# Capacitacion_SMD.net
KiCad netlist of a schematic drawn in EAGLE
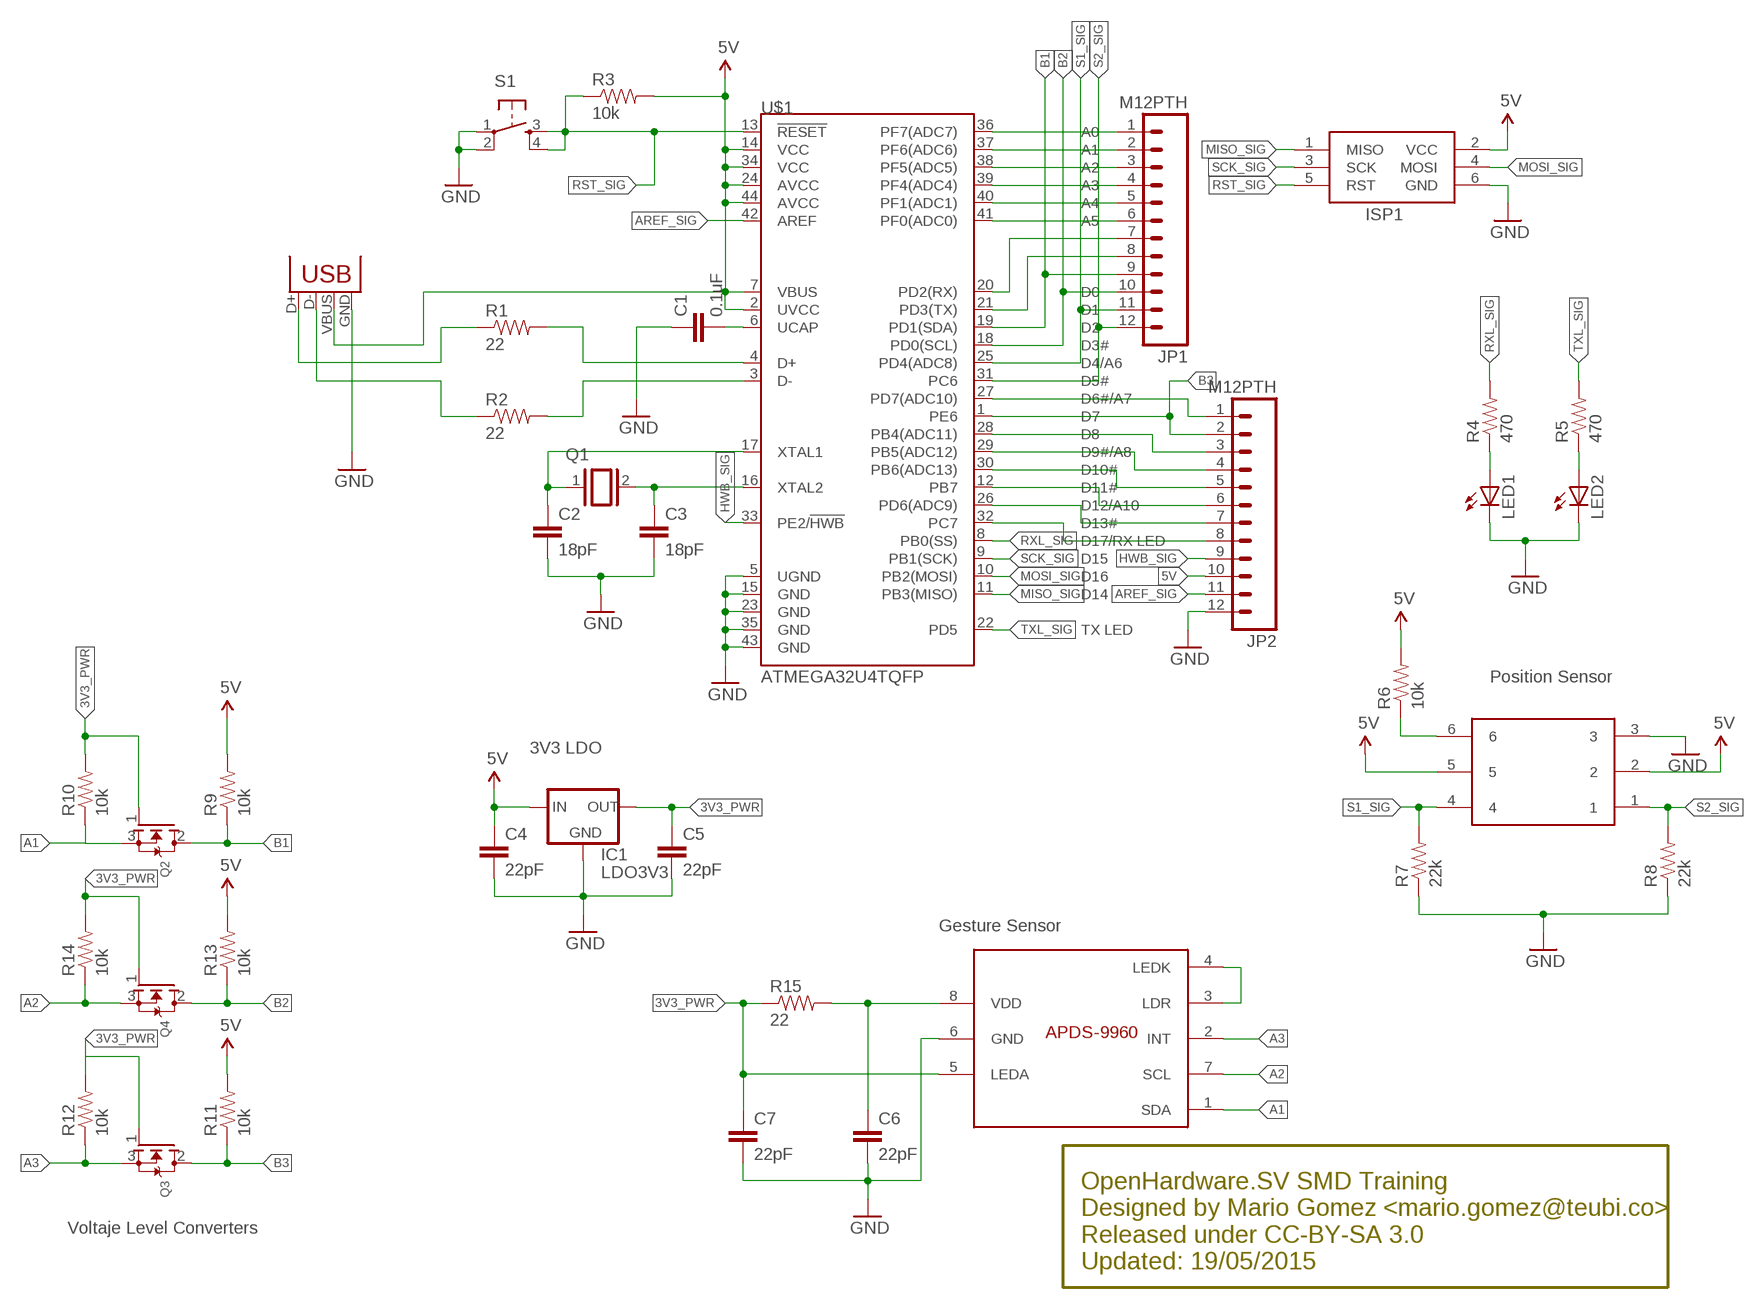
[diagram p0: schematic, sheet 1]

(export (version "E")
  (design (tool "Eeschema 10.0.6"))
  (components
    (comp (ref "C1")
      (value "0.1uF")
      (footprint "eagle-import:CAP-PTH-SMALL-KIT")
      (libsource (lib "eagle-import") (part "0.1UF-50V-20%(PTH)KIT-EZ"))
    )
    (comp (ref "C2")
      (value "18pF")
      (footprint "eagle-import:CAP-PTH-SMALL-KIT")
      (libsource (lib "eagle-import") (part "0.1UF-50V-20%(PTH)KIT-EZ"))
    )
    (comp (ref "C3")
      (value "18pF")
      (footprint "eagle-import:CAP-PTH-SMALL-KIT")
      (libsource (lib "eagle-import") (part "0.1UF-50V-20%(PTH)KIT-EZ"))
    )
    (comp (ref "C4")
      (value "22pF")
      (footprint "eagle-import:CAP-PTH-SMALL-KIT")
      (libsource (lib "eagle-import") (part "0.1UF-50V-20%(PTH)KIT-EZ"))
    )
    (comp (ref "C5")
      (value "22pF")
      (footprint "eagle-import:CAP-PTH-SMALL-KIT")
      (libsource (lib "eagle-import") (part "0.1UF-50V-20%(PTH)KIT-EZ"))
    )
    (comp (ref "C6")
      (value "22pF")
      (footprint "eagle-import:CAP-PTH-SMALL-KIT")
      (libsource (lib "eagle-import") (part "0.1UF-50V-20%(PTH)KIT-EZ"))
    )
    (comp (ref "C7")
      (value "22pF")
      (footprint "eagle-import:CAP-PTH-SMALL-KIT")
      (libsource (lib "eagle-import") (part "0.1UF-50V-20%(PTH)KIT-EZ"))
    )
    (comp (ref "IC1")
      (value "LDO3V3")
      (footprint "eagle-import:78XXL")
      (libsource (lib "eagle-import") (part "78XXL"))
    )
    (comp (ref "ISP1")
      (value "AVRISP-6")
      (footprint "eagle-import:AVRISP")
      (libsource (lib "eagle-import") (part "AVRISP-6"))
    )
    (comp (ref "JP1")
      (value "M12PTH")
      (footprint "eagle-import:1X12")
      (libsource (lib "eagle-import") (part "M12PTH"))
    )
    (comp (ref "JP2")
      (value "M12PTH")
      (footprint "eagle-import:1X12")
      (libsource (lib "eagle-import") (part "M12PTH"))
    )
    (comp (ref "LED1")
      (value "LED5MM")
      (footprint "eagle-import:LED5MM")
      (libsource (lib "eagle-import") (part "LED5MM"))
    )
    (comp (ref "LED2")
      (value "LED5MM")
      (footprint "eagle-import:LED5MM")
      (libsource (lib "eagle-import") (part "LED5MM"))
    )
    (comp (ref "Q1")
      (value "XTAL/S")
      (footprint "eagle-import:QS")
      (libsource (lib "eagle-import") (part "XTAL/S"))
    )
    (comp (ref "Q2")
      (value "MOSFET-NGDS_TO220V")
      (footprint "eagle-import:TO220V")
      (libsource (lib "eagle-import") (part "MOSFET-NGDS_TO220V"))
    )
    (comp (ref "Q3")
      (value "MOSFET-NGDS_TO220V")
      (footprint "eagle-import:TO220V")
      (libsource (lib "eagle-import") (part "MOSFET-NGDS_TO220V"))
    )
    (comp (ref "Q4")
      (value "MOSFET-NGDS_TO220V")
      (footprint "eagle-import:TO220V")
      (libsource (lib "eagle-import") (part "MOSFET-NGDS_TO220V"))
    )
    (comp (ref "R1")
      (value "22")
      (footprint "eagle-import:AXIAL-0.3")
      (libsource (lib "eagle-import") (part "RESISTORAXIAL-0.3"))
    )
    (comp (ref "R2")
      (value "22")
      (footprint "eagle-import:AXIAL-0.3")
      (libsource (lib "eagle-import") (part "RESISTORAXIAL-0.3"))
    )
    (comp (ref "R3")
      (value "10k")
      (footprint "eagle-import:AXIAL-0.3")
      (libsource (lib "eagle-import") (part "RESISTORAXIAL-0.3"))
    )
    (comp (ref "R4")
      (value "470")
      (footprint "eagle-import:AXIAL-0.3")
      (libsource (lib "eagle-import") (part "RESISTORAXIAL-0.3"))
    )
    (comp (ref "R5")
      (value "470")
      (footprint "eagle-import:AXIAL-0.3")
      (libsource (lib "eagle-import") (part "RESISTORAXIAL-0.3"))
    )
    (comp (ref "R6")
      (value "10k")
      (footprint "eagle-import:AXIAL-0.3")
      (libsource (lib "eagle-import") (part "RESISTORAXIAL-0.3"))
    )
    (comp (ref "R7")
      (value "22k")
      (footprint "eagle-import:AXIAL-0.3")
      (libsource (lib "eagle-import") (part "RESISTORAXIAL-0.3"))
    )
    (comp (ref "R8")
      (value "22k")
      (footprint "eagle-import:AXIAL-0.3")
      (libsource (lib "eagle-import") (part "RESISTORAXIAL-0.3"))
    )
    (comp (ref "R9")
      (value "10k")
      (footprint "eagle-import:AXIAL-0.3")
      (libsource (lib "eagle-import") (part "RESISTORAXIAL-0.3"))
    )
    (comp (ref "R10")
      (value "10k")
      (footprint "eagle-import:AXIAL-0.3")
      (libsource (lib "eagle-import") (part "RESISTORAXIAL-0.3"))
    )
    (comp (ref "R11")
      (value "10k")
      (footprint "eagle-import:AXIAL-0.3")
      (libsource (lib "eagle-import") (part "RESISTORAXIAL-0.3"))
    )
    (comp (ref "R12")
      (value "10k")
      (footprint "eagle-import:AXIAL-0.3")
      (libsource (lib "eagle-import") (part "RESISTORAXIAL-0.3"))
    )
    (comp (ref "R13")
      (value "10k")
      (footprint "eagle-import:AXIAL-0.3")
      (libsource (lib "eagle-import") (part "RESISTORAXIAL-0.3"))
    )
    (comp (ref "R14")
      (value "10k")
      (footprint "eagle-import:AXIAL-0.3")
      (libsource (lib "eagle-import") (part "RESISTORAXIAL-0.3"))
    )
    (comp (ref "R15")
      (value "22")
      (footprint "eagle-import:AXIAL-0.3")
      (libsource (lib "eagle-import") (part "RESISTORAXIAL-0.3"))
    )
    (comp (ref "S1")
      (value "TAC_SWITCHPTH")
      (footprint "eagle-import:TACTILE-PTH")
      (libsource (lib "eagle-import") (part "TAC_SWITCHPTH"))
    )
    (comp (ref "U$1")
      (value "ATMEGA32U4TQFP")
      (footprint "eagle-import:SPARKFUN-DIGITALIC_TQFP44")
      (libsource (lib "eagle-import") (part "ATMEGA32U4TQFP"))
    )
    (comp (ref "U$2")
      (value "USBPTH")
      (footprint "eagle-import:USB-B-PTH")
      (libsource (lib "eagle-import") (part "USBPTH"))
    )
    (comp (ref "U$3")
      (value "RPI-1031")
      (footprint "eagle-import:RPI-1031")
      (libsource (lib "eagle-import") (part "RPI-1031"))
    )
    (comp (ref "U$4")
      (value "APDS-9960")
      (footprint "eagle-import:APDS-9960")
      (libsource (lib "eagle-import") (part "APDS-9960"))
    )
  )
  (nets
    (net (code "1") (name "3V3_PWR") (class "Default")
      (node (ref "C5") (pin "1") (pinfunction "1_1") (pintype "passive"))
      (node (ref "C7") (pin "1") (pinfunction "1_1") (pintype "passive"))
      (node (ref "IC1") (pin "OUT") (pinfunction "OUT_OUT") (pintype "passive"))
      (node (ref "Q2") (pin "1") (pinfunction "G_1") (pintype "bidirectional"))
      (node (ref "Q3") (pin "1") (pinfunction "G_1") (pintype "bidirectional"))
      (node (ref "Q4") (pin "1") (pinfunction "G_1") (pintype "bidirectional"))
      (node (ref "R10") (pin "P$2") (pinfunction "2_P$2") (pintype "passive"))
      (node (ref "R12") (pin "P$2") (pinfunction "2_P$2") (pintype "passive"))
      (node (ref "R14") (pin "P$2") (pinfunction "2_P$2") (pintype "passive"))
      (node (ref "R15") (pin "P$1") (pinfunction "1_P$1") (pintype "passive"))
      (node (ref "U$4") (pin "5") (pinfunction "LEDA_5") (pintype "bidirectional"))
    )
    (net (code "2") (name "5V") (class "Default")
      (node (ref "C4") (pin "1") (pinfunction "1_1") (pintype "passive"))
      (node (ref "IC1") (pin "IN") (pinfunction "IN_IN") (pintype "input"))
      (node (ref "ISP1") (pin "2") (pinfunction "VCC_2") (pintype "power_in"))
      (node (ref "JP2") (pin "10") (pinfunction "10_10") (pintype "passive"))
      (node (ref "R11") (pin "P$2") (pinfunction "2_P$2") (pintype "passive"))
      (node (ref "R13") (pin "P$2") (pinfunction "2_P$2") (pintype "passive"))
      (node (ref "R3") (pin "P$2") (pinfunction "2_P$2") (pintype "passive"))
      (node (ref "R6") (pin "P$2") (pinfunction "2_P$2") (pintype "passive"))
      (node (ref "R9") (pin "P$2") (pinfunction "2_P$2") (pintype "passive"))
      (node (ref "U$1") (pin "14") (pinfunction "VCC_14") (pintype "bidirectional"))
      (node (ref "U$1") (pin "2") (pinfunction "UVCC_2") (pintype "bidirectional"))
      (node (ref "U$1") (pin "24") (pinfunction "AVCC_24") (pintype "bidirectional"))
      (node (ref "U$1") (pin "34") (pinfunction "VCC_34") (pintype "bidirectional"))
      (node (ref "U$1") (pin "44") (pinfunction "AVCC_44") (pintype "bidirectional"))
      (node (ref "U$1") (pin "7") (pinfunction "VBUS_7") (pintype "bidirectional"))
      (node (ref "U$2") (pin "VBUS") (pinfunction "VBUS_VBUS") (pintype "bidirectional"))
      (node (ref "U$3") (pin "2") (pinfunction "2_2") (pintype "bidirectional"))
      (node (ref "U$3") (pin "5") (pinfunction "5_5") (pintype "bidirectional"))
    )
    (net (code "3") (name "A1") (class "Default")
      (node (ref "Q2") (pin "3") (pinfunction "S_3") (pintype "bidirectional"))
      (node (ref "R10") (pin "P$1") (pinfunction "1_P$1") (pintype "passive"))
      (node (ref "U$4") (pin "1") (pinfunction "SDA_1") (pintype "bidirectional"))
    )
    (net (code "4") (name "A2") (class "Default")
      (node (ref "Q4") (pin "3") (pinfunction "S_3") (pintype "bidirectional"))
      (node (ref "R14") (pin "P$1") (pinfunction "1_P$1") (pintype "passive"))
      (node (ref "U$4") (pin "7") (pinfunction "SCL_7") (pintype "bidirectional"))
    )
    (net (code "5") (name "A3") (class "Default")
      (node (ref "Q3") (pin "3") (pinfunction "S_3") (pintype "bidirectional"))
      (node (ref "R12") (pin "P$1") (pinfunction "1_P$1") (pintype "passive"))
      (node (ref "U$4") (pin "2") (pinfunction "INT_2") (pintype "bidirectional"))
    )
    (net (code "6") (name "AREF_SIG") (class "Default")
      (node (ref "JP2") (pin "11") (pinfunction "11_11") (pintype "passive"))
      (node (ref "U$1") (pin "42") (pinfunction "AREF_42") (pintype "bidirectional"))
    )
    (net (code "7") (name "B1") (class "Default")
      (node (ref "JP1") (pin "9") (pinfunction "9_9") (pintype "passive"))
      (node (ref "Q2") (pin "2") (pinfunction "D_2") (pintype "bidirectional"))
      (node (ref "R9") (pin "P$1") (pinfunction "1_P$1") (pintype "passive"))
      (node (ref "U$1") (pin "19") (pinfunction "PD1(SDA)_19") (pintype "bidirectional"))
    )
    (net (code "8") (name "B2") (class "Default")
      (node (ref "JP1") (pin "10") (pinfunction "10_10") (pintype "passive"))
      (node (ref "Q4") (pin "2") (pinfunction "D_2") (pintype "bidirectional"))
      (node (ref "R13") (pin "P$1") (pinfunction "1_P$1") (pintype "passive"))
      (node (ref "U$1") (pin "18") (pinfunction "PD0(SCL)_18") (pintype "bidirectional"))
    )
    (net (code "9") (name "B3") (class "Default")
      (node (ref "JP2") (pin "2") (pinfunction "2_2") (pintype "passive"))
      (node (ref "Q3") (pin "2") (pinfunction "D_2") (pintype "bidirectional"))
      (node (ref "R11") (pin "P$1") (pinfunction "1_P$1") (pintype "passive"))
      (node (ref "U$1") (pin "1") (pinfunction "PE6_1") (pintype "bidirectional"))
    )
    (net (code "10") (name "GND") (class "Default")
      (node (ref "C1") (pin "1") (pinfunction "1_1") (pintype "passive"))
      (node (ref "C2") (pin "2") (pinfunction "2_2") (pintype "passive"))
      (node (ref "C3") (pin "2") (pinfunction "2_2") (pintype "passive"))
      (node (ref "C4") (pin "2") (pinfunction "2_2") (pintype "passive"))
      (node (ref "C5") (pin "2") (pinfunction "2_2") (pintype "passive"))
      (node (ref "C6") (pin "2") (pinfunction "2_2") (pintype "passive"))
      (node (ref "C7") (pin "2") (pinfunction "2_2") (pintype "passive"))
      (node (ref "IC1") (pin "GND") (pinfunction "GND_GND") (pintype "input"))
      (node (ref "ISP1") (pin "6") (pinfunction "GND_6") (pintype "power_in"))
      (node (ref "JP2") (pin "12") (pinfunction "12_12") (pintype "passive"))
      (node (ref "LED1") (pin "K") (pinfunction "C_K") (pintype "passive"))
      (node (ref "LED2") (pin "K") (pinfunction "C_K") (pintype "passive"))
      (node (ref "R7") (pin "P$1") (pinfunction "1_P$1") (pintype "passive"))
      (node (ref "R8") (pin "P$1") (pinfunction "1_P$1") (pintype "passive"))
      (node (ref "S1") (pin "1") (pinfunction "1_1") (pintype "passive"))
      (node (ref "S1") (pin "2") (pinfunction "2_2") (pintype "passive"))
      (node (ref "U$1") (pin "15") (pinfunction "GND_15") (pintype "bidirectional"))
      (node (ref "U$1") (pin "23") (pinfunction "GND_23") (pintype "bidirectional"))
      (node (ref "U$1") (pin "35") (pinfunction "GND_35") (pintype "bidirectional"))
      (node (ref "U$1") (pin "43") (pinfunction "GND_43") (pintype "bidirectional"))
      (node (ref "U$1") (pin "5") (pinfunction "UGND_5") (pintype "bidirectional"))
      (node (ref "U$2") (pin "GND") (pinfunction "GND_GND") (pintype "bidirectional"))
      (node (ref "U$3") (pin "3") (pinfunction "3_3") (pintype "bidirectional"))
      (node (ref "U$4") (pin "6") (pinfunction "GND_6") (pintype "bidirectional"))
    )
    (net (code "11") (name "HWB_SIG") (class "Default")
      (node (ref "JP2") (pin "9") (pinfunction "9_9") (pintype "passive"))
      (node (ref "U$1") (pin "33") (pinfunction "PE2/~{HWB}_33") (pintype "bidirectional"))
    )
    (net (code "12") (name "MISO_SIG") (class "Default")
      (node (ref "ISP1") (pin "1") (pinfunction "MISO_1") (pintype "input"))
      (node (ref "U$1") (pin "11") (pinfunction "PB3(MISO)_11") (pintype "bidirectional"))
    )
    (net (code "13") (name "MOSI_SIG") (class "Default")
      (node (ref "ISP1") (pin "4") (pinfunction "MOSI_4") (pintype "output"))
      (node (ref "U$1") (pin "10") (pinfunction "PB2(MOSI)_10") (pintype "bidirectional"))
    )
    (net (code "14") (name "Net-(R1-1)") (class "Default")
      (node (ref "R1") (pin "P$1") (pinfunction "1_P$1") (pintype "passive"))
      (node (ref "U$2") (pin "D+") (pinfunction "D+_D+") (pintype "bidirectional"))
    )
    (net (code "15") (name "Net-(R1-2)") (class "Default")
      (node (ref "R1") (pin "P$2") (pinfunction "2_P$2") (pintype "passive"))
      (node (ref "U$1") (pin "4") (pinfunction "D+_4") (pintype "bidirectional"))
    )
    (net (code "16") (name "Net-(R2-1)") (class "Default")
      (node (ref "R2") (pin "P$1") (pinfunction "1_P$1") (pintype "passive"))
      (node (ref "U$2") (pin "D-") (pinfunction "D-_D-") (pintype "bidirectional"))
    )
    (net (code "17") (name "Net-(R2-2)") (class "Default")
      (node (ref "R2") (pin "P$2") (pinfunction "2_P$2") (pintype "passive"))
      (node (ref "U$1") (pin "3") (pinfunction "D-_3") (pintype "bidirectional"))
    )
    (net (code "18") (name "Net-(R4-1)") (class "Default")
      (node (ref "LED1") (pin "A") (pinfunction "A_A") (pintype "passive"))
      (node (ref "R4") (pin "P$1") (pinfunction "1_P$1") (pintype "passive"))
    )
    (net (code "19") (name "Net-(R5-1)") (class "Default")
      (node (ref "LED2") (pin "A") (pinfunction "A_A") (pintype "passive"))
      (node (ref "R5") (pin "P$1") (pinfunction "1_P$1") (pintype "passive"))
    )
    (net (code "20") (name "Net-(R6-1)") (class "Default")
      (node (ref "R6") (pin "P$1") (pinfunction "1_P$1") (pintype "passive"))
      (node (ref "U$3") (pin "6") (pinfunction "6_6") (pintype "bidirectional"))
    )
    (net (code "21") (name "Net-(R15-2)") (class "Default")
      (node (ref "C6") (pin "1") (pinfunction "1_1") (pintype "passive"))
      (node (ref "R15") (pin "P$2") (pinfunction "2_P$2") (pintype "passive"))
      (node (ref "U$4") (pin "8") (pinfunction "VDD_8") (pintype "bidirectional"))
    )
    (net (code "22") (name "Net-(U$1-PB4(ADC11))") (class "Default")
      (node (ref "JP2") (pin "3") (pinfunction "3_3") (pintype "passive"))
      (node (ref "U$1") (pin "28") (pinfunction "PB4(ADC11)_28") (pintype "bidirectional"))
    )
    (net (code "23") (name "Net-(U$1-PB5(ADC12))") (class "Default")
      (node (ref "JP2") (pin "4") (pinfunction "4_4") (pintype "passive"))
      (node (ref "U$1") (pin "29") (pinfunction "PB5(ADC12)_29") (pintype "bidirectional"))
    )
    (net (code "24") (name "Net-(U$1-PB6(ADC13))") (class "Default")
      (node (ref "JP2") (pin "5") (pinfunction "5_5") (pintype "passive"))
      (node (ref "U$1") (pin "30") (pinfunction "PB6(ADC13)_30") (pintype "bidirectional"))
    )
    (net (code "25") (name "Net-(U$1-PB7)") (class "Default")
      (node (ref "JP2") (pin "6") (pinfunction "6_6") (pintype "passive"))
      (node (ref "U$1") (pin "12") (pinfunction "PB7_12") (pintype "bidirectional"))
    )
    (net (code "26") (name "Net-(U$1-PC7)") (class "Default")
      (node (ref "JP2") (pin "8") (pinfunction "8_8") (pintype "passive"))
      (node (ref "U$1") (pin "32") (pinfunction "PC7_32") (pintype "bidirectional"))
    )
    (net (code "27") (name "Net-(U$1-PD2(RX))") (class "Default")
      (node (ref "JP1") (pin "7") (pinfunction "7_7") (pintype "passive"))
      (node (ref "U$1") (pin "20") (pinfunction "PD2(RX)_20") (pintype "bidirectional"))
    )
    (net (code "28") (name "Net-(U$1-PD3(TX))") (class "Default")
      (node (ref "JP1") (pin "8") (pinfunction "8_8") (pintype "passive"))
      (node (ref "U$1") (pin "21") (pinfunction "PD3(TX)_21") (pintype "bidirectional"))
    )
    (net (code "29") (name "Net-(U$1-PD6(ADC9))") (class "Default")
      (node (ref "JP2") (pin "7") (pinfunction "7_7") (pintype "passive"))
      (node (ref "U$1") (pin "26") (pinfunction "PD6(ADC9)_26") (pintype "bidirectional"))
    )
    (net (code "30") (name "Net-(U$1-PD7(ADC10))") (class "Default")
      (node (ref "JP2") (pin "1") (pinfunction "1_1") (pintype "passive"))
      (node (ref "U$1") (pin "27") (pinfunction "PD7(ADC10)_27") (pintype "bidirectional"))
    )
    (net (code "31") (name "Net-(U$1-PF0(ADC0))") (class "Default")
      (node (ref "JP1") (pin "6") (pinfunction "6_6") (pintype "passive"))
      (node (ref "U$1") (pin "41") (pinfunction "PF0(ADC0)_41") (pintype "bidirectional"))
    )
    (net (code "32") (name "Net-(U$1-PF1(ADC1))") (class "Default")
      (node (ref "JP1") (pin "5") (pinfunction "5_5") (pintype "passive"))
      (node (ref "U$1") (pin "40") (pinfunction "PF1(ADC1)_40") (pintype "bidirectional"))
    )
    (net (code "33") (name "Net-(U$1-PF4(ADC4))") (class "Default")
      (node (ref "JP1") (pin "4") (pinfunction "4_4") (pintype "passive"))
      (node (ref "U$1") (pin "39") (pinfunction "PF4(ADC4)_39") (pintype "bidirectional"))
    )
    (net (code "34") (name "Net-(U$1-PF5(ADC5))") (class "Default")
      (node (ref "JP1") (pin "3") (pinfunction "3_3") (pintype "passive"))
      (node (ref "U$1") (pin "38") (pinfunction "PF5(ADC5)_38") (pintype "bidirectional"))
    )
    (net (code "35") (name "Net-(U$1-PF6(ADC6))") (class "Default")
      (node (ref "JP1") (pin "2") (pinfunction "2_2") (pintype "passive"))
      (node (ref "U$1") (pin "37") (pinfunction "PF6(ADC6)_37") (pintype "bidirectional"))
    )
    (net (code "36") (name "Net-(U$1-PF7(ADC7))") (class "Default")
      (node (ref "JP1") (pin "1") (pinfunction "1_1") (pintype "passive"))
      (node (ref "U$1") (pin "36") (pinfunction "PF7(ADC7)_36") (pintype "bidirectional"))
    )
    (net (code "37") (name "Net-(U$1-UCAP)") (class "Default")
      (node (ref "C1") (pin "2") (pinfunction "2_2") (pintype "passive"))
      (node (ref "U$1") (pin "6") (pinfunction "UCAP_6") (pintype "bidirectional"))
    )
    (net (code "38") (name "Net-(U$1-XTAL1)") (class "Default")
      (node (ref "C2") (pin "1") (pinfunction "1_1") (pintype "passive"))
      (node (ref "Q1") (pin "1") (pinfunction "1_1") (pintype "passive"))
      (node (ref "U$1") (pin "17") (pinfunction "XTAL1_17") (pintype "bidirectional"))
    )
    (net (code "39") (name "Net-(U$1-XTAL2)") (class "Default")
      (node (ref "C3") (pin "1") (pinfunction "1_1") (pintype "passive"))
      (node (ref "Q1") (pin "2") (pinfunction "2_2") (pintype "passive"))
      (node (ref "U$1") (pin "16") (pinfunction "XTAL2_16") (pintype "bidirectional"))
    )
    (net (code "40") (name "Net-(U$4-LDR)") (class "Default")
      (node (ref "U$4") (pin "3") (pinfunction "LDR_3") (pintype "bidirectional"))
      (node (ref "U$4") (pin "4") (pinfunction "LEDK_4") (pintype "bidirectional"))
    )
    (net (code "41") (name "RST_SIG") (class "Default")
      (node (ref "ISP1") (pin "5") (pinfunction "RST_5") (pintype "output"))
      (node (ref "R3") (pin "P$1") (pinfunction "1_P$1") (pintype "passive"))
      (node (ref "S1") (pin "3") (pinfunction "3_3") (pintype "passive"))
      (node (ref "S1") (pin "4") (pinfunction "4_4") (pintype "passive"))
      (node (ref "U$1") (pin "13") (pinfunction "~{RESET}_13") (pintype "bidirectional"))
    )
    (net (code "42") (name "RXL_SIG") (class "Default")
      (node (ref "R4") (pin "P$2") (pinfunction "2_P$2") (pintype "passive"))
      (node (ref "U$1") (pin "8") (pinfunction "PB0(SS)_8") (pintype "bidirectional"))
    )
    (net (code "43") (name "S1_SIG") (class "Default")
      (node (ref "JP1") (pin "11") (pinfunction "11_11") (pintype "passive"))
      (node (ref "R7") (pin "P$2") (pinfunction "2_P$2") (pintype "passive"))
      (node (ref "U$1") (pin "25") (pinfunction "PD4(ADC8)_25") (pintype "bidirectional"))
      (node (ref "U$3") (pin "4") (pinfunction "4_4") (pintype "bidirectional"))
    )
    (net (code "44") (name "S2_SIG") (class "Default")
      (node (ref "JP1") (pin "12") (pinfunction "12_12") (pintype "passive"))
      (node (ref "R8") (pin "P$2") (pinfunction "2_P$2") (pintype "passive"))
      (node (ref "U$1") (pin "31") (pinfunction "PC6_31") (pintype "bidirectional"))
      (node (ref "U$3") (pin "1") (pinfunction "1_1") (pintype "bidirectional"))
    )
    (net (code "45") (name "SCK_SIG") (class "Default")
      (node (ref "ISP1") (pin "3") (pinfunction "SCK_3") (pintype "output"))
      (node (ref "U$1") (pin "9") (pinfunction "PB1(SCK)_9") (pintype "bidirectional"))
    )
    (net (code "46") (name "TXL_SIG") (class "Default")
      (node (ref "R5") (pin "P$2") (pinfunction "2_P$2") (pintype "passive"))
      (node (ref "U$1") (pin "22") (pinfunction "PD5_22") (pintype "bidirectional"))
    )
  )
)
